# Peryferia.net
KiCad netlist of a schematic drawn in Altium Designer
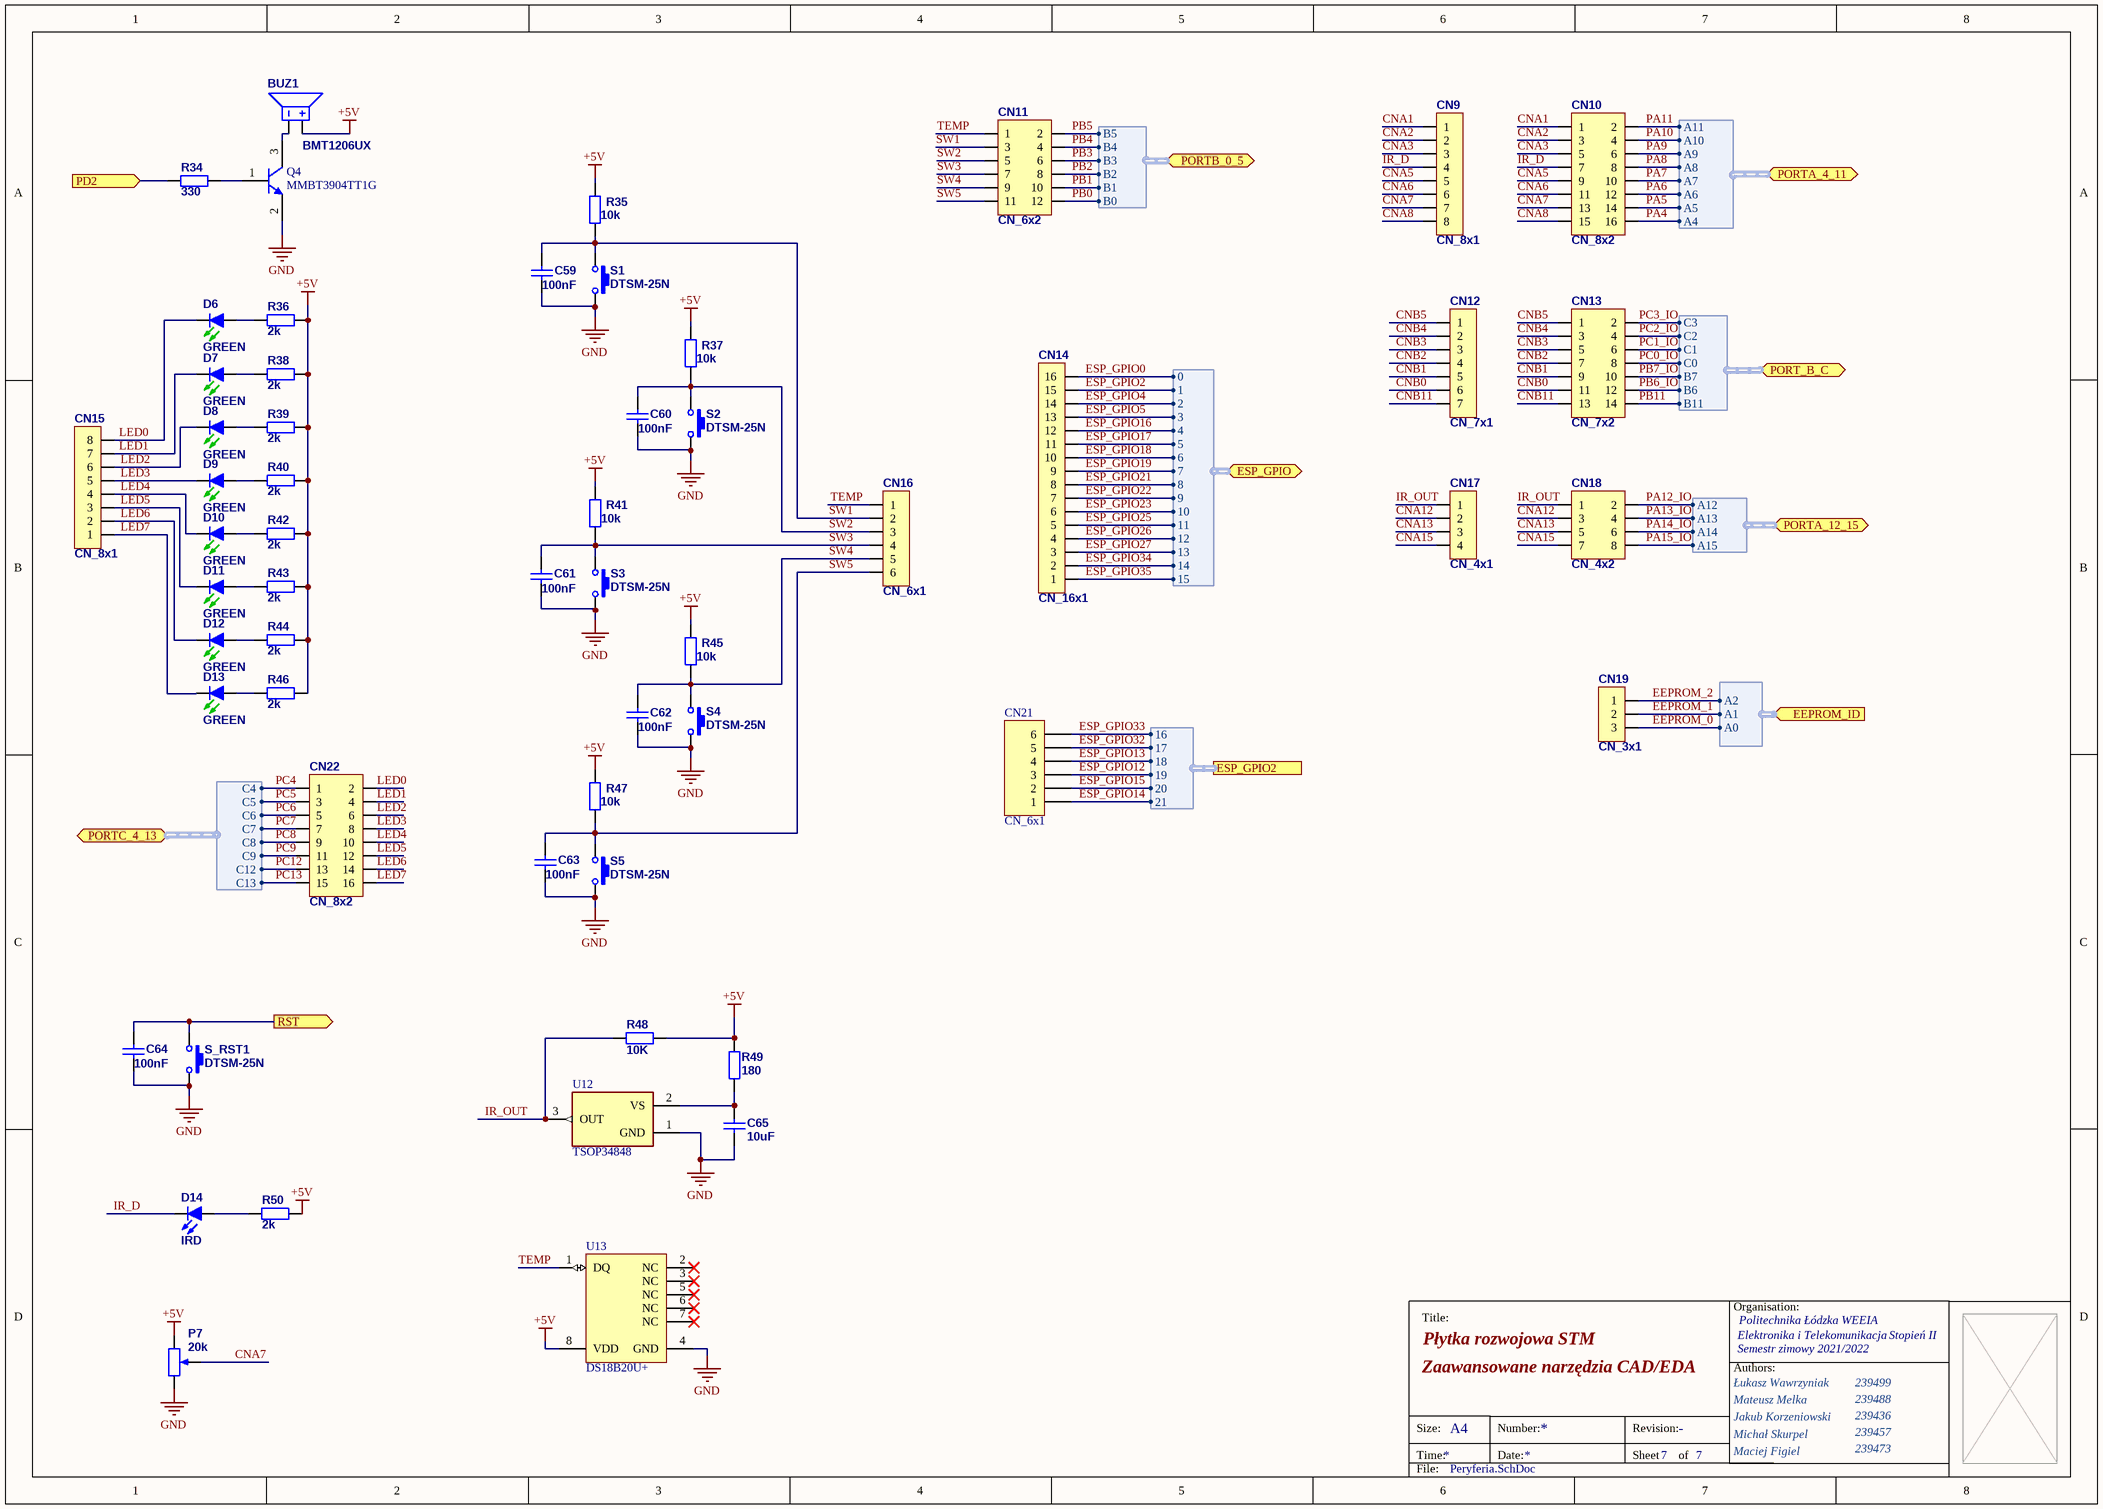
[diagram p0: Peryferia.SchDoc]

(export (version "E")
  (design (tool "Eeschema 10.0.6"))
  (components
    (comp (ref "BUZ1")
      (value "BMT1206UX")
      (footprint "Buzzer - LD-BZEG-1305")
      (description "Buzzer")
      (libsource (lib "sounders") (part "BMT1206UX"))
    )
    (comp (ref "C59")
      (value "100nF")
      (footprint "PCB1:0805")
      (description "Capacitor")
      (libsource (lib "capacitors") (part "Cap"))
    )
    (comp (ref "C60")
      (value "100nF")
      (footprint "PCB1:0805")
      (description "Capacitor")
      (libsource (lib "capacitors") (part "Cap"))
    )
    (comp (ref "C61")
      (value "100nF")
      (footprint "PCB1:0805")
      (description "Capacitor")
      (libsource (lib "capacitors") (part "Cap"))
    )
    (comp (ref "C62")
      (value "100nF")
      (footprint "PCB1:0805")
      (description "Capacitor")
      (libsource (lib "capacitors") (part "Cap"))
    )
    (comp (ref "C63")
      (value "100nF")
      (footprint "PCB1:0805")
      (description "Capacitor")
      (libsource (lib "capacitors") (part "Cap"))
    )
    (comp (ref "C64")
      (value "100nF")
      (footprint "PCB1:0805")
      (description "Capacitor")
      (libsource (lib "capacitors") (part "Cap"))
    )
    (comp (ref "C65")
      (value "10uF")
      (footprint "PCB1:0805")
      (description "Capacitor")
      (libsource (lib "capacitors") (part "Cap"))
    )
    (comp (ref "CN9") (value "CN_8x1") (footprint "GP_8x1") (libsource (lib "") (part "CN_8x1_1")))
    (comp (ref "CN10") (value "CN_8x2") (footprint "GP_8x2") (libsource (lib "goldpin_male") (part "CN_8x2")))
    (comp (ref "CN11") (value "CN_6x2") (footprint "GP_6x2") (libsource (lib "goldpin_male") (part "CN_6x2")))
    (comp (ref "CN12") (value "CN_7x1") (footprint "GP_7x1") (libsource (lib "goldpin_male") (part "CN_7x1")))
    (comp (ref "CN13") (value "CN_7x2") (footprint "GP_7x2") (libsource (lib "goldpin_male") (part "CN_7x2")))
    (comp (ref "CN14")
      (value "CN_16x1")
      (footprint "GP_16x1")
      (libsource (lib "goldpin_male") (part "CN_16x1"))
    )
    (comp (ref "CN15") (value "CN_8x1") (footprint "GP_8x1") (libsource (lib "goldpin_male") (part "CN_8x1")))
    (comp (ref "CN16") (value "CN_6x1") (footprint "GP_6x1") (libsource (lib "goldpin_male") (part "CN_6x1")))
    (comp (ref "CN17") (value "CN_4x1") (footprint "GP_4x1") (libsource (lib "goldpin_male") (part "CN_4x1")))
    (comp (ref "CN18") (value "CN_4x2") (footprint "GP_4x2") (libsource (lib "goldpin_male") (part "CN_4x2")))
    (comp (ref "CN19") (value "CN_3x1") (footprint "GP_3x1") (libsource (lib "goldpin_male") (part "CN_3x1")))
    (comp (ref "CN21")
      (value "CN_6x1")
      (footprint "HDR1X6")
      (description "Header, 6-Pin")
      (fields (field (name "PUBLISHER") "Altium Limited"))
      (libsource (lib "Miscellaneous Connectors") (part "Header 6"))
    )
    (comp (ref "CN22") (value "CN_8x2") (footprint "GP_8x2") (libsource (lib "goldpin_male") (part "CN_8x2")))
    (comp (ref "D6")
      (value "GREEN")
      (footprint "LED1206G")
      (description "GREEN LED")
      (fields (field (name "VOLTAGE") "2,2-2,5V"))
      (libsource (lib "leds") (part "LED_GREEN"))
    )
    (comp (ref "D7")
      (value "GREEN")
      (footprint "LED1206G")
      (description "GREEN LED")
      (fields (field (name "VOLTAGE") "2,2-2,5V"))
      (libsource (lib "leds") (part "LED_GREEN"))
    )
    (comp (ref "D8")
      (value "GREEN")
      (footprint "LED1206G")
      (description "GREEN LED")
      (fields (field (name "VOLTAGE") "2,2-2,5V"))
      (libsource (lib "leds") (part "LED_GREEN"))
    )
    (comp (ref "D9")
      (value "GREEN")
      (footprint "LED1206G")
      (description "GREEN LED")
      (fields (field (name "VOLTAGE") "2,2-2,5V"))
      (libsource (lib "leds") (part "LED_GREEN"))
    )
    (comp (ref "D10")
      (value "GREEN")
      (footprint "LED1206G")
      (description "GREEN LED")
      (fields (field (name "VOLTAGE") "2,2-2,5V"))
      (libsource (lib "leds") (part "LED_GREEN"))
    )
    (comp (ref "D11")
      (value "GREEN")
      (footprint "LED1206G")
      (description "GREEN LED")
      (fields (field (name "VOLTAGE") "2,2-2,5V"))
      (libsource (lib "leds") (part "LED_GREEN"))
    )
    (comp (ref "D12")
      (value "GREEN")
      (footprint "LED1206G")
      (description "GREEN LED")
      (fields (field (name "VOLTAGE") "2,2-2,5V"))
      (libsource (lib "leds") (part "LED_GREEN"))
    )
    (comp (ref "D13")
      (value "GREEN")
      (footprint "LED1206G")
      (description "GREEN LED")
      (fields (field (name "VOLTAGE") "2,2-2,5V"))
      (libsource (lib "leds") (part "LED_GREEN"))
    )
    (comp (ref "D14")
      (value "IRD")
      (footprint "LED-Polarized")
      (description "Typical RED, GREEN, YELLOW, AMBER GaAs LED")
      (libsource (lib "leds") (part "LED"))
    )
    (comp (ref "P7")
      (value "20k")
      (footprint "3305SMD")
      (description "3305SMD-10K")
      (libsource (lib "resistors") (part "3305SMD-10K"))
    )
    (comp (ref "Q4")
      (value "MMBT3904TT1G")
      (footprint "ONSC-SC-75-3-463-01_V")
      (description "General Purpose Transistor, NPN Silicon, 3-Pin SC-75, Pb-Free, Tape and Reel")
      (fields (field (name "MANUFACTURER") "On Semiconductor"))
      (libsource (lib "Altium Content Vault") (part "ONSC-NPN-B1E2C3-3"))
    )
    (comp (ref "R34")
      (value "330")
      (footprint "PCB1:0805")
      (description "Resistor")
      (libsource (lib "") (part "Res_3"))
    )
    (comp (ref "R35")
      (value "10k")
      (footprint "PCB1:0805")
      (description "Resistor")
      (libsource (lib "resistors") (part "Res"))
    )
    (comp (ref "R36")
      (value "2k")
      (footprint "PCB1:0805")
      (description "Resistor")
      (libsource (lib "") (part "Res_2"))
    )
    (comp (ref "R37")
      (value "10k")
      (footprint "PCB1:0805")
      (description "Resistor")
      (libsource (lib "resistors") (part "Res"))
    )
    (comp (ref "R38")
      (value "2k")
      (footprint "PCB1:0805")
      (description "Resistor")
      (libsource (lib "") (part "Res_2"))
    )
    (comp (ref "R39")
      (value "2k")
      (footprint "PCB1:0805")
      (description "Resistor")
      (libsource (lib "") (part "Res_2"))
    )
    (comp (ref "R40")
      (value "2k")
      (footprint "PCB1:0805")
      (description "Resistor")
      (libsource (lib "") (part "Res_2"))
    )
    (comp (ref "R41")
      (value "10k")
      (footprint "PCB1:0805")
      (description "Resistor")
      (libsource (lib "resistors") (part "Res"))
    )
    (comp (ref "R42")
      (value "2k")
      (footprint "PCB1:0805")
      (description "Resistor")
      (libsource (lib "") (part "Res_2"))
    )
    (comp (ref "R43")
      (value "2k")
      (footprint "PCB1:0805")
      (description "Resistor")
      (libsource (lib "") (part "Res_2"))
    )
    (comp (ref "R44")
      (value "2k")
      (footprint "PCB1:0805")
      (description "Resistor")
      (libsource (lib "") (part "Res_2"))
    )
    (comp (ref "R45")
      (value "10k")
      (footprint "PCB1:0805")
      (description "Resistor")
      (libsource (lib "resistors") (part "Res"))
    )
    (comp (ref "R46")
      (value "2k")
      (footprint "PCB1:0805")
      (description "Resistor")
      (libsource (lib "") (part "Res_2"))
    )
    (comp (ref "R47")
      (value "10k")
      (footprint "PCB1:0805")
      (description "Resistor")
      (libsource (lib "resistors") (part "Res"))
    )
    (comp (ref "R48")
      (value "10K")
      (footprint "PCB1:0805")
      (description "Resistor")
      (libsource (lib "") (part "Res_2"))
    )
    (comp (ref "R49")
      (value "180")
      (footprint "PCB1:0805")
      (description "Resistor")
      (libsource (lib "") (part "Res_1"))
    )
    (comp (ref "R50")
      (value "2k")
      (footprint "PCB1:0805")
      (description "Resistor")
      (libsource (lib "") (part "Res_2"))
    )
    (comp (ref "S1")
      (value "DTSM-25N")
      (footprint "DTSM-25N")
      (description "DIPTRONICS Brown 12x12mm SMD Tactile SPST-NO Switch")
      (libsource (lib "microswitches") (part "DTSM-25N"))
    )
    (comp (ref "S2")
      (value "DTSM-25N")
      (footprint "DTSM-25N")
      (description "DIPTRONICS Brown 12x12mm SMD Tactile SPST-NO Switch")
      (libsource (lib "microswitches") (part "DTSM-25N"))
    )
    (comp (ref "S3")
      (value "DTSM-25N")
      (footprint "DTSM-25N")
      (description "DIPTRONICS Brown 12x12mm SMD Tactile SPST-NO Switch")
      (libsource (lib "microswitches") (part "DTSM-25N"))
    )
    (comp (ref "S4")
      (value "DTSM-25N")
      (footprint "DTSM-25N")
      (description "DIPTRONICS Brown 12x12mm SMD Tactile SPST-NO Switch")
      (libsource (lib "microswitches") (part "DTSM-25N"))
    )
    (comp (ref "S5")
      (value "DTSM-25N")
      (footprint "DTSM-25N")
      (description "DIPTRONICS Brown 12x12mm SMD Tactile SPST-NO Switch")
      (libsource (lib "microswitches") (part "DTSM-25N"))
    )
    (comp (ref "S_RST1")
      (value "DTSM-25N")
      (footprint "DTSM-25N")
      (description "DIPTRONICS Brown 12x12mm SMD Tactile SPST-NO Switch")
      (libsource (lib "microswitches") (part "DTSM-25N"))
    )
    (comp (ref "U12")
      (value "TSOP34848")
      (footprint "Vishay_TSOP34838_0")
      (description "Remote Receiver Sensor, 36.0kHz 45m Through Hole")
      (fields (field (name "MF") "Vishay Semiconductor") (field (name "MP") "TSOP31236"))
      (libsource (lib "TSOP31236") (part "TSOP31236"))
    )
    (comp (ref "U13")
      (value "DS18B20U+")
      (footprint "MAXM-U8+1_L")
      (description "High-Precision 1-Wire Digital Thermometer, -55 to 125 degC, 8-Pin SOP (U8+1), Pb-Free")
      (fields (field (name "GENERIC PART NUMBER") "DS18B20"))
      (libsource (lib "Altium Content Vault") (part "DS18B20-U8"))
    )
  )
  (nets
    (net (code "18") (name "+5V") (class "Default")
      (node (ref "BUZ1") (pin "1") (pinfunction "1_1") (pintype "passive"))
      (node (ref "P7") (pin "2") (pinfunction "BOT_2") (pintype "passive"))
      (node (ref "R35") (pin "1") (pinfunction "1_1") (pintype "passive"))
      (node (ref "R36") (pin "1") (pinfunction "1_1") (pintype "passive"))
      (node (ref "R37") (pin "1") (pinfunction "1_1") (pintype "passive"))
      (node (ref "R38") (pin "1") (pinfunction "1_1") (pintype "passive"))
      (node (ref "R39") (pin "1") (pinfunction "1_1") (pintype "passive"))
      (node (ref "R40") (pin "1") (pinfunction "1_1") (pintype "passive"))
      (node (ref "R41") (pin "1") (pinfunction "1_1") (pintype "passive"))
      (node (ref "R42") (pin "1") (pinfunction "1_1") (pintype "passive"))
      (node (ref "R43") (pin "1") (pinfunction "1_1") (pintype "passive"))
      (node (ref "R44") (pin "1") (pinfunction "1_1") (pintype "passive"))
      (node (ref "R45") (pin "1") (pinfunction "1_1") (pintype "passive"))
      (node (ref "R46") (pin "1") (pinfunction "1_1") (pintype "passive"))
      (node (ref "R47") (pin "1") (pinfunction "1_1") (pintype "passive"))
      (node (ref "R48") (pin "1") (pinfunction "1_1") (pintype "passive"))
      (node (ref "R49") (pin "2") (pinfunction "2_2") (pintype "passive"))
      (node (ref "R50") (pin "1") (pinfunction "1_1") (pintype "passive"))
      (node (ref "U13") (pin "8") (pinfunction "VDD_8") (pintype "power_in"))
    )
    (net (code "19") (name "/CNA1") (class "Default")
      (node (ref "CN10") (pin "1") (pinfunction "1_1") (pintype "passive"))
      (node (ref "CN9") (pin "1") (pinfunction "1_1") (pintype "passive"))
    )
    (net (code "20") (name "/CNA2") (class "Default")
      (node (ref "CN10") (pin "3") (pinfunction "3_3") (pintype "passive"))
      (node (ref "CN9") (pin "2") (pinfunction "2_2") (pintype "passive"))
    )
    (net (code "21") (name "/CNA3") (class "Default")
      (node (ref "CN10") (pin "5") (pinfunction "5_5") (pintype "passive"))
      (node (ref "CN9") (pin "3") (pinfunction "3_3") (pintype "passive"))
    )
    (net (code "22") (name "/CNA5") (class "Default")
      (node (ref "CN10") (pin "9") (pinfunction "9_9") (pintype "passive"))
      (node (ref "CN9") (pin "5") (pinfunction "5_5") (pintype "passive"))
    )
    (net (code "23") (name "/CNA6") (class "Default")
      (node (ref "CN10") (pin "11") (pinfunction "11_11") (pintype "passive"))
      (node (ref "CN9") (pin "6") (pinfunction "6_6") (pintype "passive"))
    )
    (net (code "24") (name "/CNA7") (class "Default")
      (node (ref "CN10") (pin "13") (pinfunction "13_13") (pintype "passive"))
      (node (ref "CN9") (pin "7") (pinfunction "7_7") (pintype "passive"))
      (node (ref "P7") (pin "3") (pinfunction "TAP_3") (pintype "passive"))
    )
    (net (code "25") (name "/CNA8") (class "Default")
      (node (ref "CN10") (pin "15") (pinfunction "15_15") (pintype "passive"))
      (node (ref "CN9") (pin "8") (pinfunction "8_8") (pintype "passive"))
    )
    (net (code "26") (name "/CNA12") (class "Default")
      (node (ref "CN17") (pin "2") (pinfunction "2_2") (pintype "passive"))
      (node (ref "CN18") (pin "3") (pinfunction "3_3") (pintype "passive"))
    )
    (net (code "27") (name "/CNA13") (class "Default")
      (node (ref "CN17") (pin "3") (pinfunction "3_3") (pintype "passive"))
      (node (ref "CN18") (pin "5") (pinfunction "5_5") (pintype "passive"))
    )
    (net (code "28") (name "/CNA15") (class "Default")
      (node (ref "CN17") (pin "4") (pinfunction "4_4") (pintype "passive"))
      (node (ref "CN18") (pin "7") (pinfunction "7_7") (pintype "passive"))
    )
    (net (code "29") (name "/CNB0") (class "Default")
      (node (ref "CN12") (pin "6") (pinfunction "6_6") (pintype "passive"))
      (node (ref "CN13") (pin "11") (pinfunction "11_11") (pintype "passive"))
    )
    (net (code "30") (name "/CNB1") (class "Default")
      (node (ref "CN12") (pin "5") (pinfunction "5_5") (pintype "passive"))
      (node (ref "CN13") (pin "9") (pinfunction "9_9") (pintype "passive"))
    )
    (net (code "31") (name "/CNB2") (class "Default")
      (node (ref "CN12") (pin "4") (pinfunction "4_4") (pintype "passive"))
      (node (ref "CN13") (pin "7") (pinfunction "7_7") (pintype "passive"))
    )
    (net (code "32") (name "/CNB3") (class "Default")
      (node (ref "CN12") (pin "3") (pinfunction "3_3") (pintype "passive"))
      (node (ref "CN13") (pin "5") (pinfunction "5_5") (pintype "passive"))
    )
    (net (code "33") (name "/CNB4") (class "Default")
      (node (ref "CN12") (pin "2") (pinfunction "2_2") (pintype "passive"))
      (node (ref "CN13") (pin "3") (pinfunction "3_3") (pintype "passive"))
    )
    (net (code "34") (name "/CNB5") (class "Default")
      (node (ref "CN12") (pin "1") (pinfunction "1_1") (pintype "passive"))
      (node (ref "CN13") (pin "1") (pinfunction "1_1") (pintype "passive"))
    )
    (net (code "35") (name "/CNB11") (class "Default")
      (node (ref "CN12") (pin "7") (pinfunction "7_7") (pintype "passive"))
      (node (ref "CN13") (pin "13") (pinfunction "13_13") (pintype "passive"))
    )
    (net (code "36") (name "/EEPROM_0") (class "Default")
      (node (ref "CN19") (pin "3") (pinfunction "3_3") (pintype "passive"))
    )
    (net (code "37") (name "/EEPROM_1") (class "Default")
      (node (ref "CN19") (pin "2") (pinfunction "2_2") (pintype "passive"))
    )
    (net (code "38") (name "/EEPROM_2") (class "Default")
      (node (ref "CN19") (pin "1") (pinfunction "1_1") (pintype "passive"))
    )
    (net (code "39") (name "/ESP_GPIO0") (class "Default")
      (node (ref "CN14") (pin "16") (pinfunction "16_16") (pintype "passive"))
    )
    (net (code "40") (name "/ESP_GPIO2") (class "Default")
      (node (ref "CN14") (pin "15") (pinfunction "15_15") (pintype "passive"))
    )
    (net (code "41") (name "/ESP_GPIO4") (class "Default")
      (node (ref "CN14") (pin "14") (pinfunction "14_14") (pintype "passive"))
    )
    (net (code "42") (name "/ESP_GPIO5") (class "Default")
      (node (ref "CN14") (pin "13") (pinfunction "13_13") (pintype "passive"))
    )
    (net (code "43") (name "/ESP_GPIO12") (class "Default")
      (node (ref "CN21") (pin "3") (pinfunction "3_3") (pintype "passive"))
    )
    (net (code "44") (name "/ESP_GPIO13") (class "Default")
      (node (ref "CN21") (pin "4") (pinfunction "4_4") (pintype "passive"))
    )
    (net (code "45") (name "/ESP_GPIO14") (class "Default")
      (node (ref "CN21") (pin "1") (pinfunction "1_1") (pintype "passive"))
    )
    (net (code "46") (name "/ESP_GPIO15") (class "Default")
      (node (ref "CN21") (pin "2") (pinfunction "2_2") (pintype "passive"))
    )
    (net (code "47") (name "/ESP_GPIO16") (class "Default")
      (node (ref "CN14") (pin "12") (pinfunction "12_12") (pintype "passive"))
    )
    (net (code "48") (name "/ESP_GPIO17") (class "Default")
      (node (ref "CN14") (pin "11") (pinfunction "11_11") (pintype "passive"))
    )
    (net (code "49") (name "/ESP_GPIO18") (class "Default")
      (node (ref "CN14") (pin "10") (pinfunction "10_10") (pintype "passive"))
    )
    (net (code "50") (name "/ESP_GPIO19") (class "Default")
      (node (ref "CN14") (pin "9") (pinfunction "9_9") (pintype "passive"))
    )
    (net (code "51") (name "/ESP_GPIO21") (class "Default")
      (node (ref "CN14") (pin "8") (pinfunction "8_8") (pintype "passive"))
    )
    (net (code "52") (name "/ESP_GPIO22") (class "Default")
      (node (ref "CN14") (pin "7") (pinfunction "7_7") (pintype "passive"))
    )
    (net (code "53") (name "/ESP_GPIO23") (class "Default")
      (node (ref "CN14") (pin "6") (pinfunction "6_6") (pintype "passive"))
    )
    (net (code "54") (name "/ESP_GPIO25") (class "Default")
      (node (ref "CN14") (pin "5") (pinfunction "5_5") (pintype "passive"))
    )
    (net (code "55") (name "/ESP_GPIO26") (class "Default")
      (node (ref "CN14") (pin "4") (pinfunction "4_4") (pintype "passive"))
    )
    (net (code "56") (name "/ESP_GPIO27") (class "Default")
      (node (ref "CN14") (pin "3") (pinfunction "3_3") (pintype "passive"))
    )
    (net (code "57") (name "/ESP_GPIO32") (class "Default")
      (node (ref "CN21") (pin "5") (pinfunction "5_5") (pintype "passive"))
    )
    (net (code "58") (name "/ESP_GPIO33") (class "Default")
      (node (ref "CN21") (pin "6") (pinfunction "6_6") (pintype "passive"))
    )
    (net (code "59") (name "/ESP_GPIO34") (class "Default")
      (node (ref "CN14") (pin "2") (pinfunction "2_2") (pintype "passive"))
    )
    (net (code "60") (name "/ESP_GPIO35") (class "Default")
      (node (ref "CN14") (pin "1") (pinfunction "1_1") (pintype "passive"))
    )
    (net (code "61") (name "/IR_D") (class "Default")
      (node (ref "CN10") (pin "7") (pinfunction "7_7") (pintype "passive"))
      (node (ref "CN9") (pin "4") (pinfunction "4_4") (pintype "passive"))
      (node (ref "D14") (pin "2") (pinfunction "K_2") (pintype "passive"))
    )
    (net (code "62") (name "/IR_OUT") (class "Default")
      (node (ref "CN17") (pin "1") (pinfunction "1_1") (pintype "passive"))
      (node (ref "CN18") (pin "1") (pinfunction "1_1") (pintype "passive"))
      (node (ref "R48") (pin "2") (pinfunction "2_2") (pintype "passive"))
      (node (ref "U12") (pin "3") (pinfunction "OUT_3") (pintype "output"))
    )
    (net (code "63") (name "/LED0") (class "Default")
      (node (ref "CN15") (pin "8") (pinfunction "8_8") (pintype "passive"))
      (node (ref "CN22") (pin "2") (pinfunction "2_2") (pintype "passive"))
      (node (ref "D6") (pin "2") (pinfunction "K_2") (pintype "passive"))
    )
    (net (code "64") (name "/LED1") (class "Default")
      (node (ref "CN15") (pin "7") (pinfunction "7_7") (pintype "passive"))
      (node (ref "CN22") (pin "4") (pinfunction "4_4") (pintype "passive"))
      (node (ref "D7") (pin "2") (pinfunction "K_2") (pintype "passive"))
    )
    (net (code "65") (name "/LED2") (class "Default")
      (node (ref "CN15") (pin "6") (pinfunction "6_6") (pintype "passive"))
      (node (ref "CN22") (pin "6") (pinfunction "6_6") (pintype "passive"))
      (node (ref "D8") (pin "2") (pinfunction "K_2") (pintype "passive"))
    )
    (net (code "66") (name "/LED3") (class "Default")
      (node (ref "CN15") (pin "5") (pinfunction "5_5") (pintype "passive"))
      (node (ref "CN22") (pin "8") (pinfunction "8_8") (pintype "passive"))
      (node (ref "D9") (pin "2") (pinfunction "K_2") (pintype "passive"))
    )
    (net (code "67") (name "/LED4") (class "Default")
      (node (ref "CN15") (pin "4") (pinfunction "4_4") (pintype "passive"))
      (node (ref "CN22") (pin "10") (pinfunction "10_10") (pintype "passive"))
      (node (ref "D10") (pin "2") (pinfunction "K_2") (pintype "passive"))
    )
    (net (code "68") (name "/LED5") (class "Default")
      (node (ref "CN15") (pin "3") (pinfunction "3_3") (pintype "passive"))
      (node (ref "CN22") (pin "12") (pinfunction "12_12") (pintype "passive"))
      (node (ref "D11") (pin "2") (pinfunction "K_2") (pintype "passive"))
    )
    (net (code "69") (name "/LED6") (class "Default")
      (node (ref "CN15") (pin "2") (pinfunction "2_2") (pintype "passive"))
      (node (ref "CN22") (pin "14") (pinfunction "14_14") (pintype "passive"))
      (node (ref "D12") (pin "2") (pinfunction "K_2") (pintype "passive"))
    )
    (net (code "70") (name "/LED7") (class "Default")
      (node (ref "CN15") (pin "1") (pinfunction "1_1") (pintype "passive"))
      (node (ref "CN22") (pin "16") (pinfunction "16_16") (pintype "passive"))
      (node (ref "D13") (pin "2") (pinfunction "K_2") (pintype "passive"))
    )
    (net (code "71") (name "/PA4") (class "Default")
      (node (ref "CN10") (pin "16") (pinfunction "16_16") (pintype "passive"))
    )
    (net (code "72") (name "/PA5") (class "Default")
      (node (ref "CN10") (pin "14") (pinfunction "14_14") (pintype "passive"))
    )
    (net (code "73") (name "/PA6") (class "Default")
      (node (ref "CN10") (pin "12") (pinfunction "12_12") (pintype "passive"))
    )
    (net (code "74") (name "/PA7") (class "Default")
      (node (ref "CN10") (pin "10") (pinfunction "10_10") (pintype "passive"))
    )
    (net (code "75") (name "/PA8") (class "Default")
      (node (ref "CN10") (pin "8") (pinfunction "8_8") (pintype "passive"))
    )
    (net (code "76") (name "/PA9") (class "Default")
      (node (ref "CN10") (pin "6") (pinfunction "6_6") (pintype "passive"))
    )
    (net (code "77") (name "/PA10") (class "Default")
      (node (ref "CN10") (pin "4") (pinfunction "4_4") (pintype "passive"))
    )
    (net (code "78") (name "/PA11") (class "Default")
      (node (ref "CN10") (pin "2") (pinfunction "2_2") (pintype "passive"))
    )
    (net (code "79") (name "/PA12_IO") (class "Default")
      (node (ref "CN18") (pin "2") (pinfunction "2_2") (pintype "passive"))
    )
    (net (code "80") (name "/PA13_IO") (class "Default")
      (node (ref "CN18") (pin "4") (pinfunction "4_4") (pintype "passive"))
    )
    (net (code "81") (name "/PA14_IO") (class "Default")
      (node (ref "CN18") (pin "6") (pinfunction "6_6") (pintype "passive"))
    )
    (net (code "82") (name "/PA15_IO") (class "Default")
      (node (ref "CN18") (pin "8") (pinfunction "8_8") (pintype "passive"))
    )
    (net (code "83") (name "/PB0") (class "Default")
      (node (ref "CN11") (pin "12") (pinfunction "12_12") (pintype "passive"))
    )
    (net (code "84") (name "/PB1") (class "Default")
      (node (ref "CN11") (pin "10") (pinfunction "10_10") (pintype "passive"))
    )
    (net (code "85") (name "/PB2") (class "Default")
      (node (ref "CN11") (pin "8") (pinfunction "8_8") (pintype "passive"))
    )
    (net (code "86") (name "/PB3") (class "Default")
      (node (ref "CN11") (pin "6") (pinfunction "6_6") (pintype "passive"))
    )
    (net (code "87") (name "/PB4") (class "Default")
      (node (ref "CN11") (pin "4") (pinfunction "4_4") (pintype "passive"))
    )
    (net (code "88") (name "/PB5") (class "Default")
      (node (ref "CN11") (pin "2") (pinfunction "2_2") (pintype "passive"))
    )
    (net (code "89") (name "/PB6_IO") (class "Default")
      (node (ref "CN13") (pin "12") (pinfunction "12_12") (pintype "passive"))
    )
    (net (code "90") (name "/PB7_IO") (class "Default")
      (node (ref "CN13") (pin "10") (pinfunction "10_10") (pintype "passive"))
    )
    (net (code "91") (name "/PB11") (class "Default")
      (node (ref "CN13") (pin "14") (pinfunction "14_14") (pintype "passive"))
    )
    (net (code "92") (name "/PC0_IO") (class "Default")
      (node (ref "CN13") (pin "8") (pinfunction "8_8") (pintype "passive"))
    )
    (net (code "93") (name "/PC1_IO") (class "Default")
      (node (ref "CN13") (pin "6") (pinfunction "6_6") (pintype "passive"))
    )
    (net (code "94") (name "/PC2_IO") (class "Default")
      (node (ref "CN13") (pin "4") (pinfunction "4_4") (pintype "passive"))
    )
    (net (code "95") (name "/PC3_IO") (class "Default")
      (node (ref "CN13") (pin "2") (pinfunction "2_2") (pintype "passive"))
    )
    (net (code "96") (name "/PC4") (class "Default")
      (node (ref "CN22") (pin "1") (pinfunction "1_1") (pintype "passive"))
    )
    (net (code "97") (name "/PC5") (class "Default")
      (node (ref "CN22") (pin "3") (pinfunction "3_3") (pintype "passive"))
    )
    (net (code "98") (name "/PC6") (class "Default")
      (node (ref "CN22") (pin "5") (pinfunction "5_5") (pintype "passive"))
    )
    (net (code "99") (name "/PC7") (class "Default")
      (node (ref "CN22") (pin "7") (pinfunction "7_7") (pintype "passive"))
    )
    (net (code "100") (name "/PC8") (class "Default")
      (node (ref "CN22") (pin "9") (pinfunction "9_9") (pintype "passive"))
    )
    (net (code "101") (name "/PC9") (class "Default")
      (node (ref "CN22") (pin "11") (pinfunction "11_11") (pintype "passive"))
    )
    (net (code "102") (name "/PC12") (class "Default")
      (node (ref "CN22") (pin "13") (pinfunction "13_13") (pintype "passive"))
    )
    (net (code "103") (name "/PC13") (class "Default")
      (node (ref "CN22") (pin "15") (pinfunction "15_15") (pintype "passive"))
    )
    (net (code "104") (name "/PD2") (class "Default")
      (node (ref "R34") (pin "1") (pinfunction "1_1") (pintype "passive"))
    )
    (net (code "105") (name "/RST") (class "Default")
      (node (ref "C64") (pin "1") (pinfunction "1_1") (pintype "passive"))
      (node (ref "S_RST1") (pin "1") (pinfunction "1_1") (pintype "passive"))
    )
    (net (code "106") (name "/SW1") (class "Default")
      (node (ref "C59") (pin "1") (pinfunction "1_1") (pintype "passive"))
      (node (ref "CN11") (pin "3") (pinfunction "3_3") (pintype "passive"))
      (node (ref "CN16") (pin "2") (pinfunction "2_2") (pintype "passive"))
      (node (ref "R35") (pin "2") (pinfunction "2_2") (pintype "passive"))
      (node (ref "S1") (pin "1") (pinfunction "1_1") (pintype "passive"))
    )
    (net (code "107") (name "/SW2") (class "Default")
      (node (ref "C60") (pin "1") (pinfunction "1_1") (pintype "passive"))
      (node (ref "CN11") (pin "5") (pinfunction "5_5") (pintype "passive"))
      (node (ref "CN16") (pin "3") (pinfunction "3_3") (pintype "passive"))
      (node (ref "R37") (pin "2") (pinfunction "2_2") (pintype "passive"))
      (node (ref "S2") (pin "1") (pinfunction "1_1") (pintype "passive"))
    )
    (net (code "108") (name "/SW3") (class "Default")
      (node (ref "C61") (pin "1") (pinfunction "1_1") (pintype "passive"))
      (node (ref "CN11") (pin "7") (pinfunction "7_7") (pintype "passive"))
      (node (ref "CN16") (pin "4") (pinfunction "4_4") (pintype "passive"))
      (node (ref "R41") (pin "2") (pinfunction "2_2") (pintype "passive"))
      (node (ref "S3") (pin "1") (pinfunction "1_1") (pintype "passive"))
    )
    (net (code "109") (name "/SW4") (class "Default")
      (node (ref "C62") (pin "1") (pinfunction "1_1") (pintype "passive"))
      (node (ref "CN11") (pin "9") (pinfunction "9_9") (pintype "passive"))
      (node (ref "CN16") (pin "5") (pinfunction "5_5") (pintype "passive"))
      (node (ref "R45") (pin "2") (pinfunction "2_2") (pintype "passive"))
      (node (ref "S4") (pin "1") (pinfunction "1_1") (pintype "passive"))
    )
    (net (code "110") (name "/SW5") (class "Default")
      (node (ref "C63") (pin "1") (pinfunction "1_1") (pintype "passive"))
      (node (ref "CN11") (pin "11") (pinfunction "11_11") (pintype "passive"))
      (node (ref "CN16") (pin "6") (pinfunction "6_6") (pintype "passive"))
      (node (ref "R47") (pin "2") (pinfunction "2_2") (pintype "passive"))
      (node (ref "S5") (pin "1") (pinfunction "1_1") (pintype "passive"))
    )
    (net (code "111") (name "/TEMP") (class "Default")
      (node (ref "CN11") (pin "1") (pinfunction "1_1") (pintype "passive"))
      (node (ref "CN16") (pin "1") (pinfunction "1_1") (pintype "passive"))
      (node (ref "U13") (pin "1") (pinfunction "DQ_1") (pintype "bidirectional"))
    )
    (net (code "120") (name "GND") (class "Default")
      (node (ref "C59") (pin "2") (pinfunction "2_2") (pintype "passive"))
      (node (ref "C60") (pin "2") (pinfunction "2_2") (pintype "passive"))
      (node (ref "C61") (pin "2") (pinfunction "2_2") (pintype "passive"))
      (node (ref "C62") (pin "2") (pinfunction "2_2") (pintype "passive"))
      (node (ref "C63") (pin "2") (pinfunction "2_2") (pintype "passive"))
      (node (ref "C64") (pin "2") (pinfunction "2_2") (pintype "passive"))
      (node (ref "C65") (pin "1") (pinfunction "1_1") (pintype "passive"))
      (node (ref "P7") (pin "1") (pinfunction "TOP_1") (pintype "passive"))
      (node (ref "Q4") (pin "2") (pinfunction "E_2") (pintype "passive"))
      (node (ref "S1") (pin "2") (pinfunction "2_2") (pintype "passive"))
      (node (ref "S2") (pin "2") (pinfunction "2_2") (pintype "passive"))
      (node (ref "S3") (pin "2") (pinfunction "2_2") (pintype "passive"))
      (node (ref "S4") (pin "2") (pinfunction "2_2") (pintype "passive"))
      (node (ref "S5") (pin "2") (pinfunction "2_2") (pintype "passive"))
      (node (ref "S_RST1") (pin "2") (pinfunction "2_2") (pintype "passive"))
      (node (ref "U12") (pin "1") (pinfunction "GND_1") (pintype "power_in"))
      (node (ref "U13") (pin "4") (pinfunction "GND_4") (pintype "power_in"))
    )
    (net (code "121") (name "Net-(D6-A)") (class "Default")
      (node (ref "D6") (pin "1") (pinfunction "A_1") (pintype "passive"))
      (node (ref "R36") (pin "2") (pinfunction "2_2") (pintype "passive"))
    )
    (net (code "122") (name "Net-(D7-A)") (class "Default")
      (node (ref "D7") (pin "1") (pinfunction "A_1") (pintype "passive"))
      (node (ref "R38") (pin "2") (pinfunction "2_2") (pintype "passive"))
    )
    (net (code "123") (name "Net-(D8-A)") (class "Default")
      (node (ref "D8") (pin "1") (pinfunction "A_1") (pintype "passive"))
      (node (ref "R39") (pin "2") (pinfunction "2_2") (pintype "passive"))
    )
    (net (code "124") (name "Net-(D9-A)") (class "Default")
      (node (ref "D9") (pin "1") (pinfunction "A_1") (pintype "passive"))
      (node (ref "R40") (pin "2") (pinfunction "2_2") (pintype "passive"))
    )
    (net (code "125") (name "Net-(D10-A)") (class "Default")
      (node (ref "D10") (pin "1") (pinfunction "A_1") (pintype "passive"))
      (node (ref "R42") (pin "2") (pinfunction "2_2") (pintype "passive"))
    )
    (net (code "126") (name "Net-(D11-A)") (class "Default")
      (node (ref "D11") (pin "1") (pinfunction "A_1") (pintype "passive"))
      (node (ref "R43") (pin "2") (pinfunction "2_2") (pintype "passive"))
    )
    (net (code "127") (name "Net-(D12-A)") (class "Default")
      (node (ref "D12") (pin "1") (pinfunction "A_1") (pintype "passive"))
      (node (ref "R44") (pin "2") (pinfunction "2_2") (pintype "passive"))
    )
    (net (code "128") (name "Net-(D13-A)") (class "Default")
      (node (ref "D13") (pin "1") (pinfunction "A_1") (pintype "passive"))
      (node (ref "R46") (pin "2") (pinfunction "2_2") (pintype "passive"))
    )
    (net (code "129") (name "Net-(D14-A)") (class "Default")
      (node (ref "D14") (pin "1") (pinfunction "A_1") (pintype "passive"))
      (node (ref "R50") (pin "2") (pinfunction "2_2") (pintype "passive"))
    )
    (net (code "130") (name "Net-(Q4-B)") (class "Default")
      (node (ref "Q4") (pin "1") (pinfunction "B_1") (pintype "passive"))
      (node (ref "R34") (pin "2") (pinfunction "2_2") (pintype "passive"))
    )
    (net (code "131") (name "Net-(Q4-C)") (class "Default")
      (node (ref "BUZ1") (pin "2") (pinfunction "2_2") (pintype "passive"))
      (node (ref "Q4") (pin "3") (pinfunction "C_3") (pintype "passive"))
    )
    (net (code "132") (name "Net-(U12-VS)") (class "Default")
      (node (ref "C65") (pin "2") (pinfunction "2_2") (pintype "passive"))
      (node (ref "R49") (pin "1") (pinfunction "1_1") (pintype "passive"))
      (node (ref "U12") (pin "2") (pinfunction "VS_2") (pintype "power_in"))
    )
    (net (code "133") (name "unconnected-(U13-NC-Pad2)") (class "Default")
      (node (ref "U13") (pin "2") (pinfunction "NC_2") (pintype "passive+no_connect"))
    )
    (net (code "134") (name "unconnected-(U13-NC-Pad3)") (class "Default")
      (node (ref "U13") (pin "3") (pinfunction "NC_3") (pintype "passive+no_connect"))
    )
    (net (code "135") (name "unconnected-(U13-NC-Pad5)") (class "Default")
      (node (ref "U13") (pin "5") (pinfunction "NC_5") (pintype "passive+no_connect"))
    )
    (net (code "136") (name "unconnected-(U13-NC-Pad6)") (class "Default")
      (node (ref "U13") (pin "6") (pinfunction "NC_6") (pintype "passive+no_connect"))
    )
    (net (code "137") (name "unconnected-(U13-NC-Pad7)") (class "Default")
      (node (ref "U13") (pin "7") (pinfunction "NC_7") (pintype "passive+no_connect"))
    )
  )
)
